# Relay_Breakout.net
KiCad netlist of a schematic drawn in EAGLE
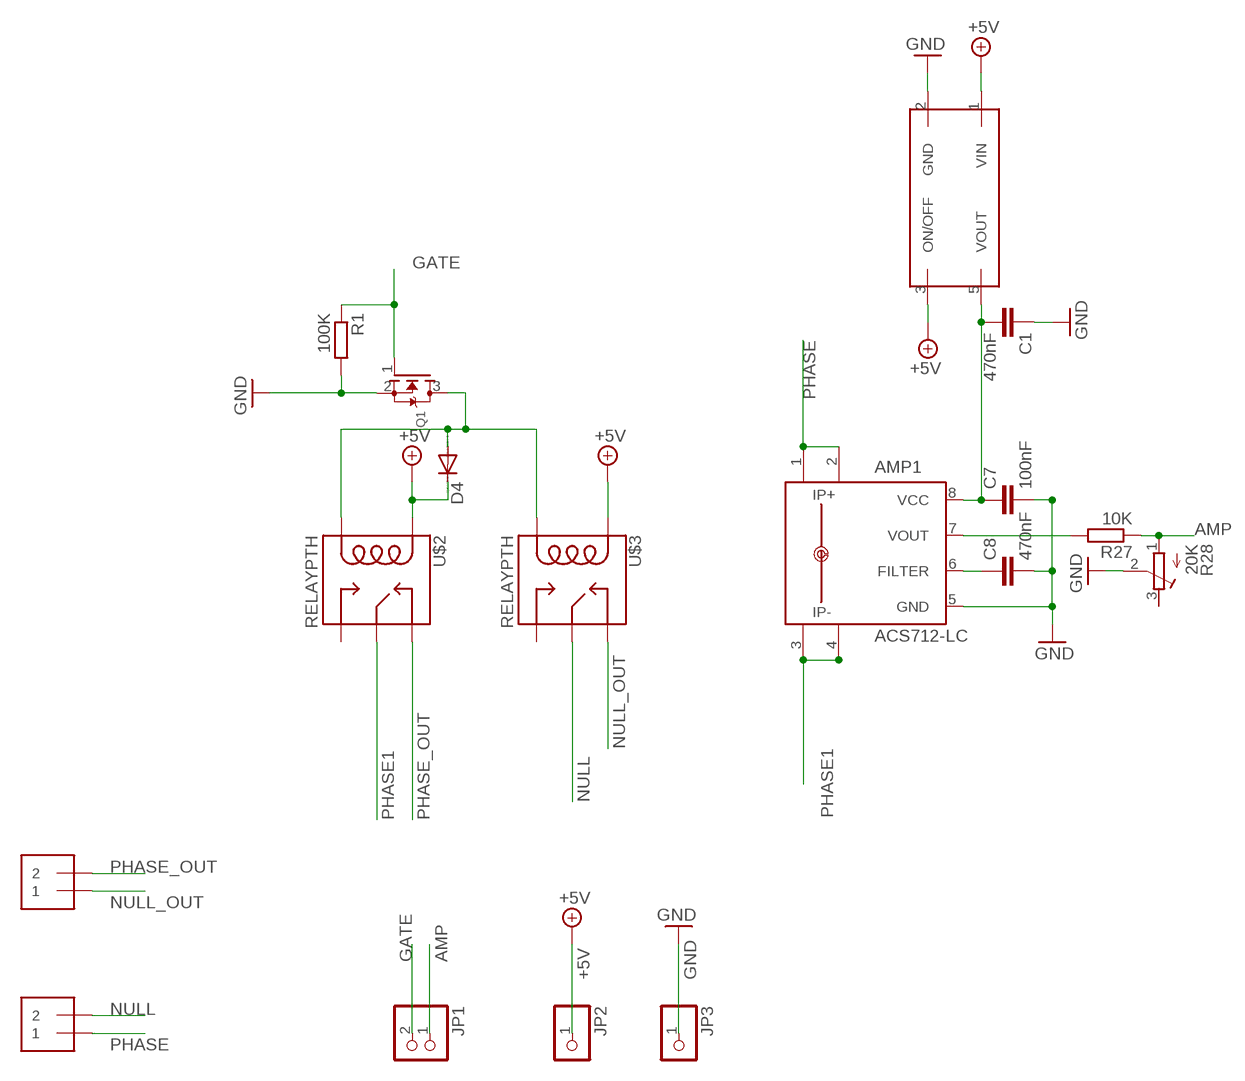
[diagram p0: schematic, sheet 1]

(export (version "E")
  (design (tool "Eeschema 10.0.6"))
  (components
    (comp (ref "4.5V_REG")
      (value "S1112")
      (footprint "eagle-import:SOT23-5")
      (libsource (lib "eagle-import") (part "S1112"))
    )
    (comp (ref "AMP1")
      (value "ACS712-LC")
      (footprint "eagle-import:SOIC8")
      (libsource (lib "eagle-import") (part "ACS712-LC"))
    )
    (comp (ref "C1")
      (value "470nF")
      (footprint "eagle-import:C0805")
      (libsource (lib "eagle-import") (part "C-EUC0805"))
    )
    (comp (ref "C7")
      (value "100nF")
      (footprint "eagle-import:C0805")
      (libsource (lib "eagle-import") (part "C-EUC0805"))
    )
    (comp (ref "C8")
      (value "470nF")
      (footprint "eagle-import:C0805")
      (libsource (lib "eagle-import") (part "C-EUC0805"))
    )
    (comp (ref "D4")
      (value "DIODE-DO-214AC")
      (footprint "eagle-import:DO-214AC")
      (libsource (lib "eagle-import") (part "DIODE-DO-214AC"))
    )
    (comp (ref "J1")
      (value "1X2-3.5MM")
      (footprint "eagle-import:1X2-3.5MM")
      (libsource (lib "eagle-import") (part "1X2-3.5MM"))
    )
    (comp (ref "J2")
      (value "1X2-3.5MM")
      (footprint "eagle-import:1X2-3.5MM")
      (libsource (lib "eagle-import") (part "1X2-3.5MM"))
    )
    (comp (ref "JP1")
      (value "PINHD-1X2")
      (footprint "eagle-import:1X02")
      (libsource (lib "eagle-import") (part "PINHD-1X2"))
    )
    (comp (ref "JP2")
      (value "PINHD-1X1")
      (footprint "eagle-import:1X01")
      (libsource (lib "eagle-import") (part "PINHD-1X1"))
    )
    (comp (ref "JP3")
      (value "PINHD-1X1")
      (footprint "eagle-import:1X01")
      (libsource (lib "eagle-import") (part "PINHD-1X1"))
    )
    (comp (ref "Q1")
      (value "MOSFET-NREFLOW")
      (footprint "eagle-import:SOT23")
      (libsource (lib "eagle-import") (part "MOSFET-NREFLOW"))
    )
    (comp (ref "R1")
      (value "100K")
      (footprint "eagle-import:R0805")
      (libsource (lib "eagle-import") (part "R-EU_R0805"))
    )
    (comp (ref "R27")
      (value "10K")
      (footprint "eagle-import:R0805")
      (libsource (lib "eagle-import") (part "R-EU_R0805"))
    )
    (comp (ref "R28")
      (value "20K")
      (footprint "eagle-import:RTRIM5X")
      (libsource (lib "eagle-import") (part "R-TRIMM5X"))
    )
    (comp (ref "U$2")
      (value "RELAYPTH")
      (footprint "eagle-import:SRD-05VDC-SL-C")
      (libsource (lib "eagle-import") (part "RELAYPTH"))
    )
    (comp (ref "U$3")
      (value "RELAYPTH")
      (footprint "eagle-import:SRD-05VDC-SL-C")
      (libsource (lib "eagle-import") (part "RELAYPTH"))
    )
  )
  (nets
    (net (code "1") (name "+5V") (class "Default")
      (node (ref "4.5V_REG") (pin "1") (pinfunction "VIN_1") (pintype "power_in"))
      (node (ref "4.5V_REG") (pin "3") (pinfunction "ON/OFF_3") (pintype "input"))
      (node (ref "D4") (pin "C") (pinfunction "C_C") (pintype "passive"))
      (node (ref "JP2") (pin "1") (pinfunction "1_1") (pintype "passive"))
      (node (ref "U$2") (pin "COIL1") (pinfunction "COIL1_COIL1") (pintype "bidirectional"))
      (node (ref "U$3") (pin "COIL1") (pinfunction "COIL1_COIL1") (pintype "bidirectional"))
    )
    (net (code "2") (name "/AMP") (class "Default")
      (node (ref "JP1") (pin "1") (pinfunction "1_1") (pintype "passive"))
      (node (ref "R27") (pin "1") (pinfunction "1_1") (pintype "passive"))
      (node (ref "R28") (pin "1") (pinfunction "A_1") (pintype "passive"))
    )
    (net (code "3") (name "/GATE") (class "Default")
      (node (ref "JP1") (pin "2") (pinfunction "2_2") (pintype "passive"))
      (node (ref "Q1") (pin "1") (pinfunction "G_1") (pintype "bidirectional"))
      (node (ref "R1") (pin "1") (pinfunction "1_1") (pintype "passive"))
    )
    (net (code "4") (name "/NULL") (class "Default")
      (node (ref "J1") (pin "2") (pinfunction "2_2") (pintype "passive"))
      (node (ref "U$3") (pin "SWCOMMON") (pinfunction "SWCOMMON_SWCOMMON") (pintype "bidirectional"))
    )
    (net (code "5") (name "/NULL_OUT") (class "Default")
      (node (ref "J2") (pin "1") (pinfunction "1_1") (pintype "passive"))
      (node (ref "U$3") (pin "SWCLOSED") (pinfunction "SWCLOSE_SWCLOSED") (pintype "bidirectional"))
    )
    (net (code "6") (name "/PHASE") (class "Default")
      (node (ref "AMP1") (pin "1") (pinfunction "IP+_1") (pintype "passive"))
      (node (ref "AMP1") (pin "2") (pinfunction "IP+1_2") (pintype "passive"))
      (node (ref "J1") (pin "1") (pinfunction "1_1") (pintype "passive"))
    )
    (net (code "7") (name "/PHASE1") (class "Default")
      (node (ref "AMP1") (pin "3") (pinfunction "IP-_3") (pintype "passive"))
      (node (ref "AMP1") (pin "4") (pinfunction "IP-1_4") (pintype "passive"))
      (node (ref "U$2") (pin "SWCOMMON") (pinfunction "SWCOMMON_SWCOMMON") (pintype "bidirectional"))
    )
    (net (code "8") (name "/PHASE_OUT") (class "Default")
      (node (ref "J2") (pin "2") (pinfunction "2_2") (pintype "passive"))
      (node (ref "U$2") (pin "SWCLOSED") (pinfunction "SWCLOSE_SWCLOSED") (pintype "bidirectional"))
    )
    (net (code "9") (name "GND") (class "Default")
      (node (ref "4.5V_REG") (pin "2") (pinfunction "GND_2") (pintype "power_in"))
      (node (ref "AMP1") (pin "5") (pinfunction "GND_5") (pintype "power_in"))
      (node (ref "C1") (pin "1") (pinfunction "1_1") (pintype "passive"))
      (node (ref "C7") (pin "2") (pinfunction "2_2") (pintype "passive"))
      (node (ref "C8") (pin "2") (pinfunction "2_2") (pintype "passive"))
      (node (ref "JP3") (pin "1") (pinfunction "1_1") (pintype "passive"))
      (node (ref "Q1") (pin "2") (pinfunction "S_2") (pintype "bidirectional"))
      (node (ref "R1") (pin "2") (pinfunction "2_2") (pintype "passive"))
      (node (ref "R28") (pin "2") (pinfunction "S_2") (pintype "passive"))
    )
    (net (code "10") (name "Net-(4.5V_REG-VOUT)") (class "Default")
      (node (ref "4.5V_REG") (pin "5") (pinfunction "VOUT_5") (pintype "output"))
      (node (ref "AMP1") (pin "8") (pinfunction "VCC_8") (pintype "power_in"))
      (node (ref "C1") (pin "2") (pinfunction "2_2") (pintype "passive"))
      (node (ref "C7") (pin "1") (pinfunction "1_1") (pintype "passive"))
    )
    (net (code "11") (name "Net-(AMP1-FILTER)") (class "Default")
      (node (ref "AMP1") (pin "6") (pinfunction "FILTER_6") (pintype "bidirectional"))
      (node (ref "C8") (pin "1") (pinfunction "1_1") (pintype "passive"))
    )
    (net (code "12") (name "Net-(AMP1-VOUT)") (class "Default")
      (node (ref "AMP1") (pin "7") (pinfunction "VOUT_7") (pintype "output"))
      (node (ref "R27") (pin "2") (pinfunction "2_2") (pintype "passive"))
    )
    (net (code "13") (name "Net-(Q1-D)") (class "Default")
      (node (ref "D4") (pin "A") (pinfunction "A_A") (pintype "passive"))
      (node (ref "Q1") (pin "3") (pinfunction "D_3") (pintype "bidirectional"))
      (node (ref "U$2") (pin "COIL0") (pinfunction "COIL0_COIL0") (pintype "bidirectional"))
      (node (ref "U$3") (pin "COIL0") (pinfunction "COIL0_COIL0") (pintype "bidirectional"))
    )
    (net (code "14") (name "unconnected-(R28-E-Pad3)") (class "Default")
      (node (ref "R28") (pin "3") (pinfunction "E_3") (pintype "passive"))
    )
    (net (code "15") (name "unconnected-(U$2-PadSWOPEN)") (class "Default")
      (node (ref "U$2") (pin "SWOPEN") (pinfunction "SWOPEN_SWOPEN") (pintype "bidirectional"))
    )
    (net (code "16") (name "unconnected-(U$3-PadSWOPEN)") (class "Default")
      (node (ref "U$3") (pin "SWOPEN") (pinfunction "SWOPEN_SWOPEN") (pintype "bidirectional"))
    )
  )
)
